# FluoShield.net
KiCad netlist of a schematic drawn in EAGLE
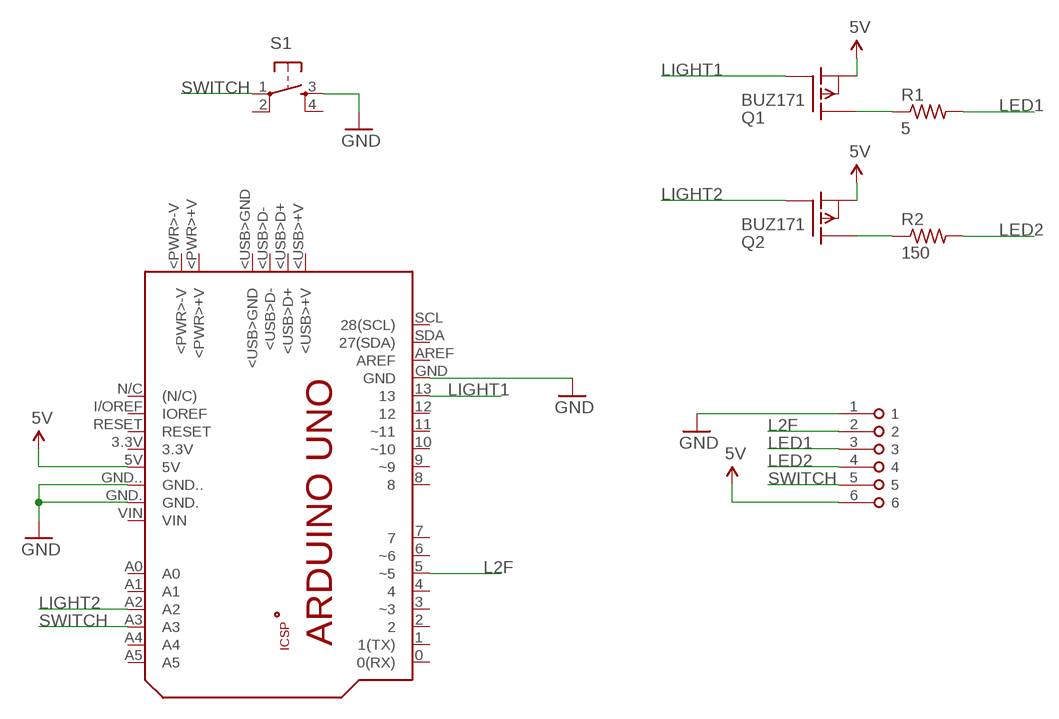
[diagram p0: schematic, sheet 1]

(export (version "E")
  (design (tool "Eeschema 10.0.6"))
  (components
    (comp (ref "PCB1")
      (value "ARDUINO_UNO")
      (footprint "eagle-import:ARDUINO_UNO")
      (libsource (lib "eagle-import") (part "ARDUINO_UNO"))
    )
    (comp (ref "Q1")
      (value "BUZ171")
      (footprint "eagle-import:TO220")
      (libsource (lib "eagle-import") (part "BUZ171"))
    )
    (comp (ref "Q2")
      (value "BUZ171")
      (footprint "eagle-import:TO220")
      (libsource (lib "eagle-import") (part "BUZ171"))
    )
    (comp (ref "R1")
      (value "5")
      (footprint "eagle-import:0207_10")
      (libsource (lib "eagle-import") (part "R-US_0207/10"))
    )
    (comp (ref "R2")
      (value "150")
      (footprint "eagle-import:0207_10")
      (libsource (lib "eagle-import") (part "R-US_0207/10"))
    )
    (comp (ref "S1")
      (value "TAC_SWITCHPTH")
      (footprint "eagle-import:TACTILE-PTH")
      (libsource (lib "eagle-import") (part "TAC_SWITCHPTH"))
    )
    (comp (ref "U$4")
      (value "TERMINAL-6")
      (footprint "eagle-import:MBE-156")
      (libsource (lib "eagle-import") (part "TERMINAL-6"))
    )
  )
  (nets
    (net (code "1") (name "/L2F") (class "Default")
      (node (ref "PCB1") (pin "5") (pinfunction "~{5}_5") (pintype "bidirectional"))
      (node (ref "U$4") (pin "2") (pinfunction "2_2") (pintype "bidirectional"))
    )
    (net (code "2") (name "/LED1") (class "Default")
      (node (ref "R1") (pin "2") (pinfunction "2_2") (pintype "passive"))
      (node (ref "U$4") (pin "3") (pinfunction "3_3") (pintype "bidirectional"))
    )
    (net (code "3") (name "/LED2") (class "Default")
      (node (ref "R2") (pin "2") (pinfunction "2_2") (pintype "passive"))
      (node (ref "U$4") (pin "4") (pinfunction "4_4") (pintype "bidirectional"))
    )
    (net (code "4") (name "/LIGHT1") (class "Default")
      (node (ref "PCB1") (pin "13") (pinfunction "13_13") (pintype "bidirectional"))
      (node (ref "Q1") (pin "1") (pinfunction "G_1") (pintype "passive"))
    )
    (net (code "5") (name "/LIGHT2") (class "Default")
      (node (ref "PCB1") (pin "A2") (pinfunction "A2_A2") (pintype "bidirectional"))
      (node (ref "Q2") (pin "1") (pinfunction "G_1") (pintype "passive"))
    )
    (net (code "6") (name "/SWITCH") (class "Default")
      (node (ref "PCB1") (pin "A3") (pinfunction "A3_A3") (pintype "bidirectional"))
      (node (ref "S1") (pin "1") (pinfunction "1_1") (pintype "passive"))
      (node (ref "U$4") (pin "5") (pinfunction "5_5") (pintype "bidirectional"))
    )
    (net (code "7") (name "5V") (class "Default")
      (node (ref "PCB1") (pin "5V") (pinfunction "5V_5V") (pintype "bidirectional"))
      (node (ref "Q1") (pin "3") (pinfunction "S_3") (pintype "passive"))
      (node (ref "Q2") (pin "3") (pinfunction "S_3") (pintype "passive"))
      (node (ref "U$4") (pin "6") (pinfunction "6_6") (pintype "bidirectional"))
    )
    (net (code "8") (name "GND") (class "Default")
      (node (ref "PCB1") (pin "GND") (pinfunction "GND_GND") (pintype "bidirectional"))
      (node (ref "PCB1") (pin "GND.") (pinfunction "GND._GND.") (pintype "bidirectional"))
      (node (ref "PCB1") (pin "GND..") (pinfunction "GND.._GND..") (pintype "bidirectional"))
      (node (ref "S1") (pin "3") (pinfunction "3_3") (pintype "passive"))
      (node (ref "U$4") (pin "1") (pinfunction "1_1") (pintype "bidirectional"))
    )
    (net (code "9") (name "Net-(Q1-D)") (class "Default")
      (node (ref "Q1") (pin "2") (pinfunction "D_2") (pintype "passive"))
      (node (ref "R1") (pin "1") (pinfunction "1_1") (pintype "passive"))
    )
    (net (code "10") (name "Net-(Q2-D)") (class "Default")
      (node (ref "Q2") (pin "2") (pinfunction "D_2") (pintype "passive"))
      (node (ref "R2") (pin "1") (pinfunction "1_1") (pintype "passive"))
    )
    (net (code "11") (name "unconnected-(PCB1-(N{slash}C)-PadN{slash}C)") (class "Default")
      (node (ref "PCB1") (pin "N/C") (pinfunction "(N/C)_N/C") (pintype "bidirectional"))
    )
    (net (code "12") (name "unconnected-(PCB1-0(RX)-Pad0)") (class "Default")
      (node (ref "PCB1") (pin "0") (pinfunction "0(RX)_0") (pintype "bidirectional"))
    )
    (net (code "13") (name "unconnected-(PCB1-1(TX)-Pad1)") (class "Default")
      (node (ref "PCB1") (pin "1") (pinfunction "1(TX)_1") (pintype "bidirectional"))
    )
    (net (code "14") (name "unconnected-(PCB1-27(SDA)-PadSDA)") (class "Default")
      (node (ref "PCB1") (pin "SDA") (pinfunction "27(SDA)_SDA") (pintype "bidirectional"))
    )
    (net (code "15") (name "unconnected-(PCB1-28(SCL)-PadSCL)") (class "Default")
      (node (ref "PCB1") (pin "SCL") (pinfunction "28(SCL)_SCL") (pintype "bidirectional"))
    )
    (net (code "16") (name "unconnected-(PCB1-IOREF-PadI{slash}OREF)") (class "Default")
      (node (ref "PCB1") (pin "I/OREF") (pinfunction "IOREF_I/OREF") (pintype "bidirectional"))
    )
    (net (code "17") (name "unconnected-(PCB1-Pad+5V)") (class "Default")
      (node (ref "PCB1") (pin "+5V") (pinfunction "+5V_+5V") (pintype "bidirectional"))
    )
    (net (code "18") (name "unconnected-(PCB1-Pad2)") (class "Default")
      (node (ref "PCB1") (pin "2") (pinfunction "2_2") (pintype "bidirectional"))
    )
    (net (code "19") (name "unconnected-(PCB1-Pad3.3V)") (class "Default")
      (node (ref "PCB1") (pin "3.3V") (pinfunction "3.3V_3.3V") (pintype "bidirectional"))
    )
    (net (code "20") (name "unconnected-(PCB1-Pad4)") (class "Default")
      (node (ref "PCB1") (pin "4") (pinfunction "4_4") (pintype "bidirectional"))
    )
    (net (code "21") (name "unconnected-(PCB1-Pad7)") (class "Default")
      (node (ref "PCB1") (pin "7") (pinfunction "7_7") (pintype "bidirectional"))
    )
    (net (code "22") (name "unconnected-(PCB1-Pad8)") (class "Default")
      (node (ref "PCB1") (pin "8") (pinfunction "8_8") (pintype "bidirectional"))
    )
    (net (code "23") (name "unconnected-(PCB1-Pad12)") (class "Default")
      (node (ref "PCB1") (pin "12") (pinfunction "12_12") (pintype "bidirectional"))
    )
    (net (code "24") (name "unconnected-(PCB1-Pad<PWR>+V)") (class "Default")
      (node (ref "PCB1") (pin "<PWR>+V") (pinfunction "<PWR>+V_<PWR>+V") (pintype "bidirectional"))
    )
    (net (code "25") (name "unconnected-(PCB1-Pad<PWR>-V)") (class "Default")
      (node (ref "PCB1") (pin "<PWR>-V") (pinfunction "<PWR>-V_<PWR>-V") (pintype "bidirectional"))
    )
    (net (code "26") (name "unconnected-(PCB1-Pad<USB>+V)") (class "Default")
      (node (ref "PCB1") (pin "<USB>+V") (pinfunction "<USB>+V_<USB>+V") (pintype "bidirectional"))
    )
    (net (code "27") (name "unconnected-(PCB1-Pad<USB>D+)") (class "Default")
      (node (ref "PCB1") (pin "<USB>D+") (pinfunction "<USB>D+_<USB>D+") (pintype "bidirectional"))
    )
    (net (code "28") (name "unconnected-(PCB1-Pad<USB>D-)") (class "Default")
      (node (ref "PCB1") (pin "<USB>D-") (pinfunction "<USB>D-_<USB>D-") (pintype "bidirectional"))
    )
    (net (code "29") (name "unconnected-(PCB1-Pad<USB>GND)") (class "Default")
      (node (ref "PCB1") (pin "<USB>GND") (pinfunction "<USB>GND_<USB>GND") (pintype "bidirectional"))
    )
    (net (code "30") (name "unconnected-(PCB1-PadA0)") (class "Default")
      (node (ref "PCB1") (pin "A0") (pinfunction "A0_A0") (pintype "bidirectional"))
    )
    (net (code "31") (name "unconnected-(PCB1-PadA1)") (class "Default")
      (node (ref "PCB1") (pin "A1") (pinfunction "A1_A1") (pintype "bidirectional"))
    )
    (net (code "32") (name "unconnected-(PCB1-PadA4)") (class "Default")
      (node (ref "PCB1") (pin "A4") (pinfunction "A4_A4") (pintype "bidirectional"))
    )
    (net (code "33") (name "unconnected-(PCB1-PadA5)") (class "Default")
      (node (ref "PCB1") (pin "A5") (pinfunction "A5_A5") (pintype "bidirectional"))
    )
    (net (code "34") (name "unconnected-(PCB1-PadAREF)") (class "Default")
      (node (ref "PCB1") (pin "AREF") (pinfunction "AREF_AREF") (pintype "bidirectional"))
    )
    (net (code "35") (name "unconnected-(PCB1-PadGND_)") (class "Default")
      (node (ref "PCB1") (pin "GND_") (pinfunction "GND__GND_") (pintype "bidirectional"))
    )
    (net (code "36") (name "unconnected-(PCB1-PadMISO)") (class "Default")
      (node (ref "PCB1") (pin "MISO") (pinfunction "MISO_MISO") (pintype "bidirectional"))
    )
    (net (code "37") (name "unconnected-(PCB1-PadMOSI)") (class "Default")
      (node (ref "PCB1") (pin "MOSI") (pinfunction "MOSI_MOSI") (pintype "bidirectional"))
    )
    (net (code "38") (name "unconnected-(PCB1-PadRESET)") (class "Default")
      (node (ref "PCB1") (pin "RESET") (pinfunction "RESET_RESET") (pintype "bidirectional"))
    )
    (net (code "39") (name "unconnected-(PCB1-PadRESET.)") (class "Default")
      (node (ref "PCB1") (pin "RESET.") (pinfunction "RESET._RESET.") (pintype "bidirectional"))
    )
    (net (code "40") (name "unconnected-(PCB1-PadSCK)") (class "Default")
      (node (ref "PCB1") (pin "SCK") (pinfunction "SCK_SCK") (pintype "bidirectional"))
    )
    (net (code "41") (name "unconnected-(PCB1-PadVIN)") (class "Default")
      (node (ref "PCB1") (pin "VIN") (pinfunction "VIN_VIN") (pintype "bidirectional"))
    )
    (net (code "42") (name "unconnected-(PCB1-~{3}-Pad3)") (class "Default")
      (node (ref "PCB1") (pin "3") (pinfunction "~{3}_3") (pintype "bidirectional"))
    )
    (net (code "43") (name "unconnected-(PCB1-~{6}-Pad6)") (class "Default")
      (node (ref "PCB1") (pin "6") (pinfunction "~{6}_6") (pintype "bidirectional"))
    )
    (net (code "44") (name "unconnected-(PCB1-~{9}-Pad9)") (class "Default")
      (node (ref "PCB1") (pin "9") (pinfunction "~{9}_9") (pintype "bidirectional"))
    )
    (net (code "45") (name "unconnected-(PCB1-~{10}-Pad10)") (class "Default")
      (node (ref "PCB1") (pin "10") (pinfunction "~{10}_10") (pintype "bidirectional"))
    )
    (net (code "46") (name "unconnected-(PCB1-~{11}-Pad11)") (class "Default")
      (node (ref "PCB1") (pin "11") (pinfunction "~{11}_11") (pintype "bidirectional"))
    )
    (net (code "47") (name "unconnected-(S1-Pad2)") (class "Default")
      (node (ref "S1") (pin "2") (pinfunction "2_2") (pintype "passive"))
    )
    (net (code "48") (name "unconnected-(S1-Pad4)") (class "Default")
      (node (ref "S1") (pin "4") (pinfunction "4_4") (pintype "passive"))
    )
  )
)
